# 06_POWER_3.net
KiCad netlist of a schematic drawn in Altium Designer
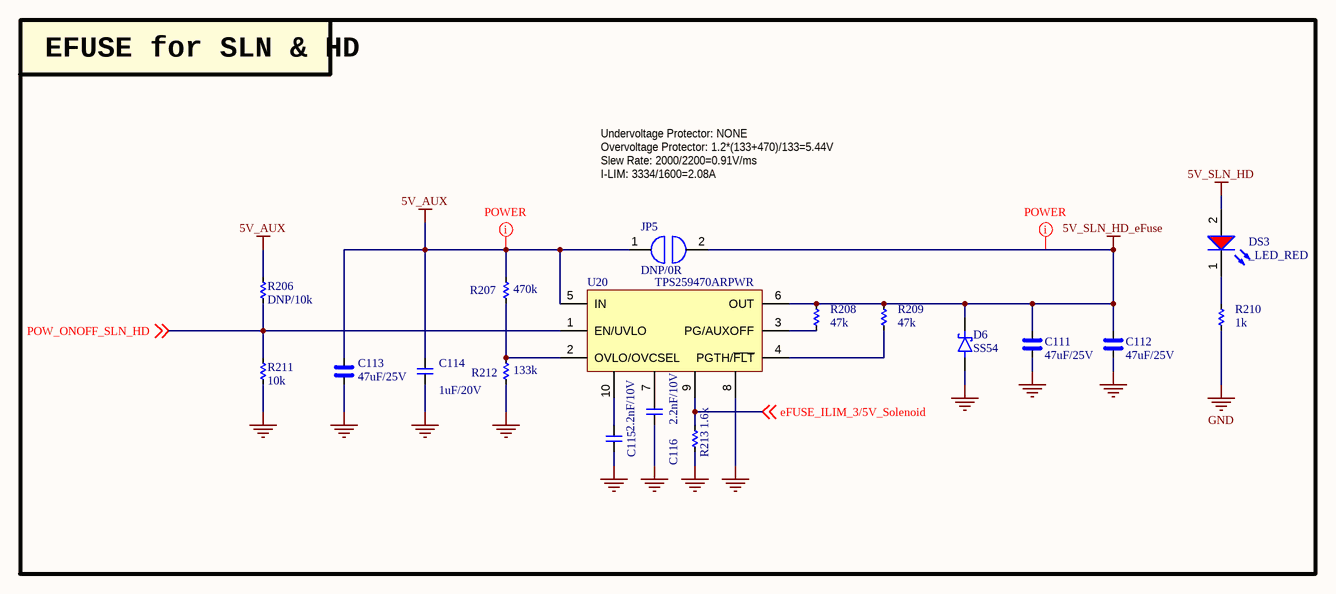
[diagram p0: 06_POWER_3.SchDoc]

(export (version "E")
  (design (tool "Eeschema 10.0.6"))
  (components
    (comp (ref "C111")
      (value "47uF/25V")
      (footprint "CAP_C_3225X80")
      (description "CAP High Value")
      (libsource (lib "LABLIB") (part "_CAP_C_High_2"))
    )
    (comp (ref "C112")
      (value "47uF/25V")
      (footprint "CAP_C_3225X80")
      (description "CAP High Value")
      (libsource (lib "LABLIB") (part "_CAP_C_High_2"))
    )
    (comp (ref "C113")
      (value "47uF/25V")
      (footprint "CAP_C_3225X80")
      (description "CAP High Value")
      (libsource (lib "LABLIB") (part "_CAP_C_High_2"))
    )
    (comp (ref "C114")
      (value "1uF/20V")
      (footprint "CAP_C_1005X60")
      (description "CAP")
      (libsource (lib "LABLIB") (part "_CAP_C_2"))
    )
    (comp (ref "C115")
      (value "2.2nF/10V")
      (footprint "CAP_C_1005X60")
      (description "CAP")
      (libsource (lib "LABLIB") (part "_CAP_C_2"))
    )
    (comp (ref "C116")
      (value "2.2nF/10V")
      (footprint "CAP_C_1005X60")
      (description "CAP")
      (libsource (lib "LABLIB") (part "_CAP_C_2"))
    )
    (comp (ref "D6")
      (value "SS54")
      (footprint "DO-214AC_SMA")
      (description "DIODE SCHOTTKY")
      (libsource (lib "LABLIB") (part "DIODE SCHOTTKY"))
    )
    (comp (ref "DS3") (value "_LED_RED") (footprint "LED_0603") (libsource (lib "LABLIB") (part "_LED_RED")))
    (comp (ref "JP5") (value "DNP/0R") (footprint "JUMPER_1608") (libsource (lib "EXP_V1") (part "JUMPER")))
    (comp (ref "R206")
      (value "DNP/10k")
      (footprint "RES_C_1005X40")
      (description "RES")
      (libsource (lib "LABLIB") (part "_RES_B_2"))
    )
    (comp (ref "R207")
      (value "470k")
      (footprint "RES_C_1005X40")
      (description "RES")
      (libsource (lib "LABLIB") (part "_RES_B_2"))
    )
    (comp (ref "R208")
      (value "47k")
      (footprint "RES_C_1005X40")
      (description "RES")
      (libsource (lib "LABLIB") (part "_RES_B_2"))
    )
    (comp (ref "R209")
      (value "47k")
      (footprint "RES_C_1005X40")
      (description "RES")
      (libsource (lib "LABLIB") (part "_RES_B_2"))
    )
    (comp (ref "R210")
      (value "1k")
      (footprint "RES_C_1005X40")
      (description "RES")
      (libsource (lib "LABLIB") (part "_RES_B_2"))
    )
    (comp (ref "R211")
      (value "10k")
      (footprint "RES_C_1005X40")
      (description "RES")
      (libsource (lib "LABLIB") (part "_RES_B_2"))
    )
    (comp (ref "R212")
      (value "133k")
      (footprint "RES_C_1005X40")
      (description "RES")
      (libsource (lib "LABLIB") (part "_RES_B_2"))
    )
    (comp (ref "R213")
      (value "1.6k")
      (footprint "RES_C_1005X40")
      (description "RES")
      (libsource (lib "LABLIB") (part "_RES_B_2"))
    )
    (comp (ref "U20")
      (value "TPS259470ARPWR")
      (footprint "VQFN-HR-10")
      (libsource (lib "EXP_HW_V3") (part "TPS259470ARPWR"))
    )
  )
  (nets
    (net (code "1") (name "5V_AUX") (class "Default")
      (node (ref "C113") (pin "2") (pinfunction "2_2") (pintype "passive"))
      (node (ref "C114") (pin "2") (pinfunction "2_2") (pintype "passive"))
      (node (ref "JP5") (pin "1") (pinfunction "1_1") (pintype "passive"))
      (node (ref "R206") (pin "1") (pinfunction "1_1") (pintype "passive"))
      (node (ref "R207") (pin "2") (pinfunction "2_2") (pintype "passive"))
      (node (ref "U20") (pin "5") (pinfunction "IN_5") (pintype "passive"))
    )
    (net (code "2") (name "5V_SLN_HD") (class "Default")
      (node (ref "DS3") (pin "2") (pinfunction "A_2") (pintype "passive"))
    )
    (net (code "3") (name "5V_SLN_HD_eFuse") (class "Default")
      (node (ref "C111") (pin "2") (pinfunction "2_2") (pintype "passive"))
      (node (ref "C112") (pin "2") (pinfunction "2_2") (pintype "passive"))
      (node (ref "D6") (pin "1") (pinfunction "K_1") (pintype "passive"))
      (node (ref "JP5") (pin "2") (pinfunction "2_2") (pintype "passive"))
      (node (ref "R208") (pin "2") (pinfunction "2_2") (pintype "passive"))
      (node (ref "R209") (pin "2") (pinfunction "2_2") (pintype "passive"))
      (node (ref "U20") (pin "6") (pinfunction "OUT_6") (pintype "passive"))
    )
    (net (code "4") (name "GND") (class "Default")
      (node (ref "C111") (pin "1") (pinfunction "1_1") (pintype "passive"))
      (node (ref "C112") (pin "1") (pinfunction "1_1") (pintype "passive"))
      (node (ref "C113") (pin "1") (pinfunction "1_1") (pintype "passive"))
      (node (ref "C114") (pin "1") (pinfunction "1_1") (pintype "passive"))
      (node (ref "C115") (pin "1") (pinfunction "1_1") (pintype "passive"))
      (node (ref "C116") (pin "1") (pinfunction "1_1") (pintype "passive"))
      (node (ref "D6") (pin "2") (pinfunction "A_2") (pintype "passive"))
      (node (ref "R210") (pin "1") (pinfunction "1_1") (pintype "passive"))
      (node (ref "R211") (pin "2") (pinfunction "2_2") (pintype "passive"))
      (node (ref "R212") (pin "1") (pinfunction "1_1") (pintype "passive"))
      (node (ref "R213") (pin "1") (pinfunction "1_1") (pintype "passive"))
      (node (ref "U20") (pin "8") (pinfunction "8_8") (pintype "passive"))
    )
    (net (code "5") (name "Net-(C115-Pad2)") (class "Default")
      (node (ref "C115") (pin "2") (pinfunction "2_2") (pintype "passive"))
      (node (ref "U20") (pin "10") (pinfunction "10_10") (pintype "passive"))
    )
    (net (code "6") (name "Net-(C116-Pad2)") (class "Default")
      (node (ref "C116") (pin "2") (pinfunction "2_2") (pintype "passive"))
      (node (ref "U20") (pin "7") (pinfunction "7_7") (pintype "passive"))
    )
    (net (code "7") (name "Net-(DS3-K)") (class "Default")
      (node (ref "DS3") (pin "1") (pinfunction "K_1") (pintype "passive"))
      (node (ref "R210") (pin "2") (pinfunction "2_2") (pintype "passive"))
    )
    (net (code "8") (name "Net-(U20-OVLO{slash}OVCSEL)") (class "Default")
      (node (ref "R207") (pin "1") (pinfunction "1_1") (pintype "passive"))
      (node (ref "R212") (pin "2") (pinfunction "2_2") (pintype "passive"))
      (node (ref "U20") (pin "2") (pinfunction "OVLO/OVCSEL_2") (pintype "passive"))
    )
    (net (code "9") (name "Net-(U20-PGTH{slash}~{FLT})") (class "Default")
      (node (ref "R209") (pin "1") (pinfunction "1_1") (pintype "passive"))
      (node (ref "U20") (pin "4") (pinfunction "PGTH/~{FLT}_4") (pintype "passive"))
    )
    (net (code "10") (name "Net-(U20-PG{slash}AUXOFF)") (class "Default")
      (node (ref "R208") (pin "1") (pinfunction "1_1") (pintype "passive"))
      (node (ref "U20") (pin "3") (pinfunction "PG/AUXOFF_3") (pintype "passive"))
    )
    (net (code "11") (name "POW_ONOFF_SLN_HD") (class "Default")
      (node (ref "R206") (pin "2") (pinfunction "2_2") (pintype "passive"))
      (node (ref "R211") (pin "1") (pinfunction "1_1") (pintype "passive"))
      (node (ref "U20") (pin "1") (pinfunction "EN/UVLO_1") (pintype "passive"))
    )
    (net (code "12") (name "eFUSE_ILIM_3{slash}5V_Solenoid") (class "Default")
      (node (ref "R213") (pin "2") (pinfunction "2_2") (pintype "passive"))
      (node (ref "U20") (pin "9") (pinfunction "9_9") (pintype "passive"))
    )
  )
)
